# sensor_board2.net
KiCad netlist of a schematic drawn in EAGLE
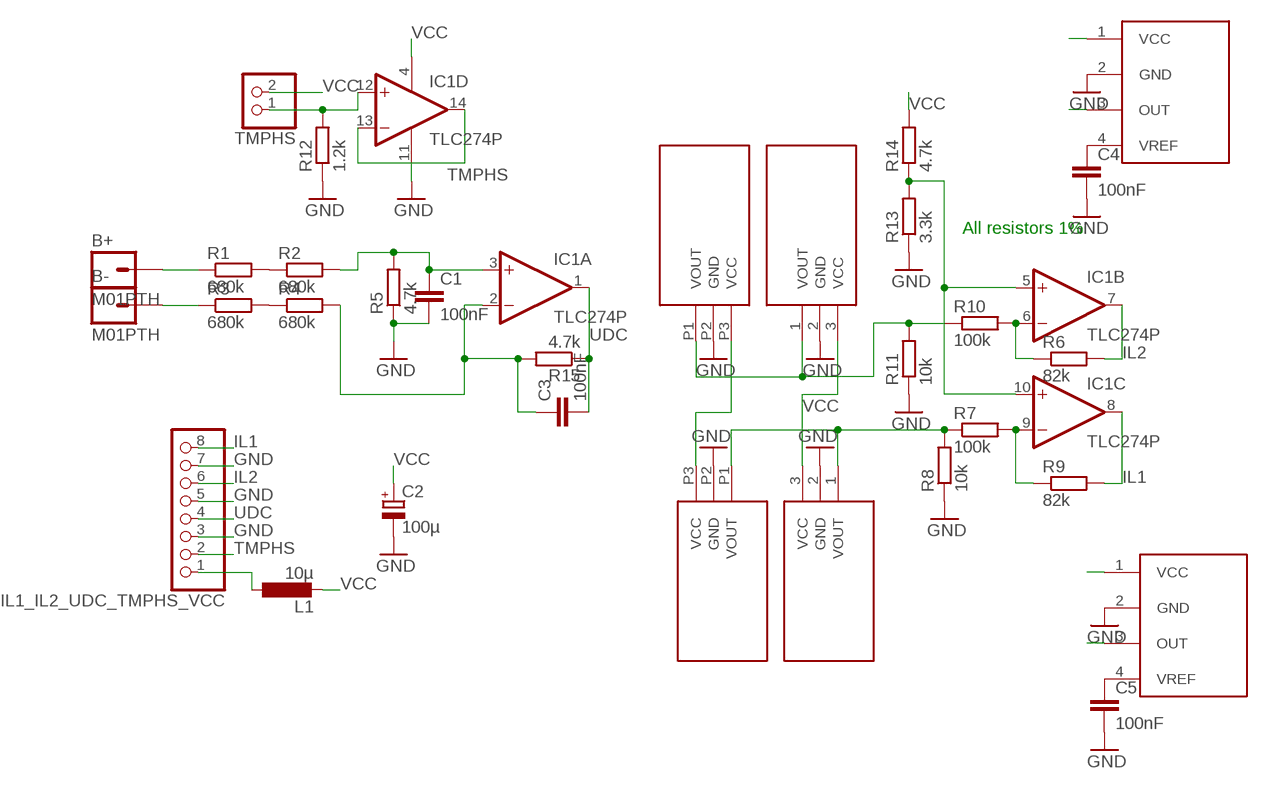
[diagram p0: schematic, sheet 1]

(export (version "E")
  (design (tool "Eeschema 10.0.6"))
  (components
    (comp (ref "B+")
      (value "M01PTH")
      (footprint "eagle-import:1X01")
      (libsource (lib "eagle-import") (part "M01PTH"))
    )
    (comp (ref "B-")
      (value "M01PTH")
      (footprint "eagle-import:1X01")
      (libsource (lib "eagle-import") (part "M01PTH"))
    )
    (comp (ref "C1")
      (value "100nF")
      (footprint "eagle-import:C025-024X044")
      (libsource (lib "eagle-import") (part "C-EU025-024X044"))
    )
    (comp (ref "C2")
      (value "100µ")
      (footprint "eagle-import:E2,5-6E")
      (libsource (lib "eagle-import") (part "CPOL-EUE2,5-6E"))
    )
    (comp (ref "C3")
      (value "100nF")
      (footprint "eagle-import:C025-024X044")
      (libsource (lib "eagle-import") (part "C-EU025-024X044"))
    )
    (comp (ref "C4")
      (value "100nF")
      (footprint "eagle-import:C025-024X044")
      (libsource (lib "eagle-import") (part "C-EU025-024X044"))
    )
    (comp (ref "C5")
      (value "100nF")
      (footprint "eagle-import:C025-024X044")
      (libsource (lib "eagle-import") (part "C-EU025-024X044"))
    )
    (comp (ref "IC1")
      (value "TLC274P")
      (footprint "eagle-import:DIL14")
      (libsource (lib "eagle-import") (part "TLC274P"))
    )
    (comp (ref "IL1_IL2_UDC_TMPHS_VCC")
      (value "PINHD-1X8")
      (footprint "eagle-import:1X08")
      (libsource (lib "eagle-import") (part "PINHD-1X8"))
    )
    (comp (ref "L1")
      (value "10µ")
      (footprint "eagle-import:0207_12")
      (libsource (lib "eagle-import") (part "L-EU0207/12"))
    )
    (comp (ref "R1")
      (value "680k")
      (footprint "eagle-import:0207_10")
      (libsource (lib "eagle-import") (part "R-EU_0207/10"))
    )
    (comp (ref "R2")
      (value "680k")
      (footprint "eagle-import:0207_10")
      (libsource (lib "eagle-import") (part "R-EU_0207/10"))
    )
    (comp (ref "R3")
      (value "680k")
      (footprint "eagle-import:0207_10")
      (libsource (lib "eagle-import") (part "R-EU_0207/10"))
    )
    (comp (ref "R4")
      (value "680k")
      (footprint "eagle-import:0207_10")
      (libsource (lib "eagle-import") (part "R-EU_0207/10"))
    )
    (comp (ref "R5")
      (value "4.7k")
      (footprint "eagle-import:0207_10")
      (libsource (lib "eagle-import") (part "R-EU_0207/10"))
    )
    (comp (ref "R6")
      (value "82k")
      (footprint "eagle-import:0207_10")
      (libsource (lib "eagle-import") (part "R-EU_0207/10"))
    )
    (comp (ref "R7")
      (value "100k")
      (footprint "eagle-import:0207_10")
      (libsource (lib "eagle-import") (part "R-EU_0207/10"))
    )
    (comp (ref "R8")
      (value "10k")
      (footprint "eagle-import:0207_10")
      (libsource (lib "eagle-import") (part "R-EU_0207/10"))
    )
    (comp (ref "R9")
      (value "82k")
      (footprint "eagle-import:0207_10")
      (libsource (lib "eagle-import") (part "R-EU_0207/10"))
    )
    (comp (ref "R10")
      (value "100k")
      (footprint "eagle-import:0207_10")
      (libsource (lib "eagle-import") (part "R-EU_0207/10"))
    )
    (comp (ref "R11")
      (value "10k")
      (footprint "eagle-import:0207_10")
      (libsource (lib "eagle-import") (part "R-EU_0207/10"))
    )
    (comp (ref "R12")
      (value "1.2k")
      (footprint "eagle-import:0207_10")
      (libsource (lib "eagle-import") (part "R-EU_0207/10"))
    )
    (comp (ref "R13")
      (value "3.3k")
      (footprint "eagle-import:0207_10")
      (libsource (lib "eagle-import") (part "R-EU_0207/10"))
    )
    (comp (ref "R14")
      (value "4.7k")
      (footprint "eagle-import:0207_10")
      (libsource (lib "eagle-import") (part "R-EU_0207/10"))
    )
    (comp (ref "R15")
      (value "4.7k")
      (footprint "eagle-import:0207_10")
      (libsource (lib "eagle-import") (part "R-EU_0207/10"))
    )
    (comp (ref "TMPHS")
      (value "PINHD-1X2")
      (footprint "eagle-import:1X02")
      (libsource (lib "eagle-import") (part "PINHD-1X2"))
    )
    (comp (ref "U$1")
      (value "TAMURA_L01Z_S05")
      (footprint "eagle-import:TAMURA_L01Z_S05")
      (libsource (lib "eagle-import") (part "TAMURA_L01Z_S05"))
    )
    (comp (ref "U$2")
      (value "TAMURA_L01Z_S05")
      (footprint "eagle-import:TAMURA_L01Z_S05")
      (libsource (lib "eagle-import") (part "TAMURA_L01Z_S05"))
    )
    (comp (ref "U$3")
      (value "HTFS")
      (footprint "eagle-import:HTFS")
      (libsource (lib "eagle-import") (part "HTFS"))
    )
    (comp (ref "U$4")
      (value "HTFS")
      (footprint "eagle-import:HTFS")
      (libsource (lib "eagle-import") (part "HTFS"))
    )
    (comp (ref "U$5")
      (value "TAMURA_L06P_S05L06P")
      (footprint "eagle-import:TAMURA_L06P_S05")
      (libsource (lib "eagle-import") (part "TAMURA_L06P_S05L06P"))
    )
    (comp (ref "U$6")
      (value "TAMURA_L06P_S05L06P")
      (footprint "eagle-import:TAMURA_L06P_S05")
      (libsource (lib "eagle-import") (part "TAMURA_L06P_S05L06P"))
    )
  )
  (nets
    (net (code "1") (name "/IL1") (class "Default")
      (node (ref "IC1") (pin "8") (pinfunction "OUT_8") (pintype "output"))
      (node (ref "IL1_IL2_UDC_TMPHS_VCC") (pin "8") (pinfunction "8_8") (pintype "passive"))
      (node (ref "R9") (pin "2") (pinfunction "2_2") (pintype "passive"))
    )
    (net (code "2") (name "/IL2") (class "Default")
      (node (ref "IC1") (pin "7") (pinfunction "OUT_7") (pintype "output"))
      (node (ref "IL1_IL2_UDC_TMPHS_VCC") (pin "6") (pinfunction "6_6") (pintype "passive"))
      (node (ref "R6") (pin "2") (pinfunction "2_2") (pintype "passive"))
    )
    (net (code "3") (name "/TMPHS") (class "Default")
      (node (ref "IC1") (pin "13") (pinfunction "-IN_13") (pintype "input"))
      (node (ref "IC1") (pin "14") (pinfunction "OUT_14") (pintype "output"))
      (node (ref "IL1_IL2_UDC_TMPHS_VCC") (pin "2") (pinfunction "2_2") (pintype "passive"))
    )
    (net (code "4") (name "/UDC") (class "Default")
      (node (ref "C3") (pin "2") (pinfunction "2_2") (pintype "passive"))
      (node (ref "IC1") (pin "1") (pinfunction "OUT_1") (pintype "output"))
      (node (ref "IL1_IL2_UDC_TMPHS_VCC") (pin "4") (pinfunction "4_4") (pintype "passive"))
      (node (ref "R15") (pin "1") (pinfunction "1_1") (pintype "passive"))
    )
    (net (code "5") (name "/VCC") (class "Default")
      (node (ref "C2") (pin "+") (pinfunction "+_+") (pintype "passive"))
      (node (ref "IC1") (pin "4") (pinfunction "V+_4") (pintype "power_in"))
      (node (ref "L1") (pin "2") (pinfunction "2_2") (pintype "passive"))
      (node (ref "R14") (pin "2") (pinfunction "2_2") (pintype "passive"))
      (node (ref "TMPHS") (pin "2") (pinfunction "2_2") (pintype "passive"))
      (node (ref "U$1") (pin "3") (pinfunction "VCC_3") (pintype "bidirectional"))
      (node (ref "U$2") (pin "3") (pinfunction "VCC_3") (pintype "bidirectional"))
      (node (ref "U$3") (pin "1") (pinfunction "VCC_1") (pintype "bidirectional"))
      (node (ref "U$4") (pin "1") (pinfunction "VCC_1") (pintype "bidirectional"))
      (node (ref "U$5") (pin "P3") (pinfunction "VCC_P3") (pintype "bidirectional"))
      (node (ref "U$6") (pin "P3") (pinfunction "VCC_P3") (pintype "bidirectional"))
    )
    (net (code "6") (name "/VOUT1") (class "Default")
      (node (ref "R7") (pin "1") (pinfunction "1_1") (pintype "passive"))
      (node (ref "R8") (pin "2") (pinfunction "2_2") (pintype "passive"))
      (node (ref "U$2") (pin "1") (pinfunction "VOUT_1") (pintype "bidirectional"))
      (node (ref "U$4") (pin "3") (pinfunction "OUT_3") (pintype "bidirectional"))
      (node (ref "U$6") (pin "P1") (pinfunction "VOUT_P1") (pintype "bidirectional"))
    )
    (net (code "7") (name "/VOUT2") (class "Default")
      (node (ref "R10") (pin "1") (pinfunction "1_1") (pintype "passive"))
      (node (ref "R11") (pin "2") (pinfunction "2_2") (pintype "passive"))
      (node (ref "U$1") (pin "1") (pinfunction "VOUT_1") (pintype "bidirectional"))
      (node (ref "U$3") (pin "3") (pinfunction "OUT_3") (pintype "bidirectional"))
      (node (ref "U$5") (pin "P1") (pinfunction "VOUT_P1") (pintype "bidirectional"))
    )
    (net (code "8") (name "GND") (class "Default")
      (node (ref "C1") (pin "2") (pinfunction "2_2") (pintype "passive"))
      (node (ref "C2") (pin "-") (pinfunction "-_-") (pintype "passive"))
      (node (ref "C4") (pin "2") (pinfunction "2_2") (pintype "passive"))
      (node (ref "C5") (pin "2") (pinfunction "2_2") (pintype "passive"))
      (node (ref "IC1") (pin "11") (pinfunction "V-_11") (pintype "power_in"))
      (node (ref "IL1_IL2_UDC_TMPHS_VCC") (pin "3") (pinfunction "3_3") (pintype "passive"))
      (node (ref "IL1_IL2_UDC_TMPHS_VCC") (pin "5") (pinfunction "5_5") (pintype "passive"))
      (node (ref "IL1_IL2_UDC_TMPHS_VCC") (pin "7") (pinfunction "7_7") (pintype "passive"))
      (node (ref "R11") (pin "1") (pinfunction "1_1") (pintype "passive"))
      (node (ref "R12") (pin "1") (pinfunction "1_1") (pintype "passive"))
      (node (ref "R13") (pin "1") (pinfunction "1_1") (pintype "passive"))
      (node (ref "R5") (pin "1") (pinfunction "1_1") (pintype "passive"))
      (node (ref "R8") (pin "1") (pinfunction "1_1") (pintype "passive"))
      (node (ref "U$1") (pin "2") (pinfunction "GND_2") (pintype "bidirectional"))
      (node (ref "U$2") (pin "2") (pinfunction "GND_2") (pintype "bidirectional"))
      (node (ref "U$3") (pin "2") (pinfunction "GND_2") (pintype "bidirectional"))
      (node (ref "U$4") (pin "2") (pinfunction "GND_2") (pintype "bidirectional"))
      (node (ref "U$5") (pin "P2") (pinfunction "GND_P2") (pintype "bidirectional"))
      (node (ref "U$6") (pin "P2") (pinfunction "GND_P2") (pintype "bidirectional"))
    )
    (net (code "9") (name "Net-(B+-Pad1)") (class "Default")
      (node (ref "B+") (pin "1") (pinfunction "1_1") (pintype "passive"))
      (node (ref "R1") (pin "1") (pinfunction "1_1") (pintype "passive"))
    )
    (net (code "10") (name "Net-(B--Pad1)") (class "Default")
      (node (ref "B-") (pin "1") (pinfunction "1_1") (pintype "passive"))
      (node (ref "R3") (pin "1") (pinfunction "1_1") (pintype "passive"))
    )
    (net (code "11") (name "Net-(IC1A-+IN)") (class "Default")
      (node (ref "C1") (pin "1") (pinfunction "1_1") (pintype "passive"))
      (node (ref "IC1") (pin "3") (pinfunction "+IN_3") (pintype "input"))
      (node (ref "R2") (pin "2") (pinfunction "2_2") (pintype "passive"))
      (node (ref "R5") (pin "2") (pinfunction "2_2") (pintype "passive"))
    )
    (net (code "12") (name "Net-(IC1A--IN)") (class "Default")
      (node (ref "C3") (pin "1") (pinfunction "1_1") (pintype "passive"))
      (node (ref "IC1") (pin "2") (pinfunction "-IN_2") (pintype "input"))
      (node (ref "R15") (pin "2") (pinfunction "2_2") (pintype "passive"))
      (node (ref "R4") (pin "2") (pinfunction "2_2") (pintype "passive"))
    )
    (net (code "13") (name "Net-(IC1B-+IN)") (class "Default")
      (node (ref "IC1") (pin "10") (pinfunction "+IN_10") (pintype "input"))
      (node (ref "IC1") (pin "5") (pinfunction "+IN_5") (pintype "input"))
      (node (ref "R13") (pin "2") (pinfunction "2_2") (pintype "passive"))
      (node (ref "R14") (pin "1") (pinfunction "1_1") (pintype "passive"))
    )
    (net (code "14") (name "Net-(IC1B--IN)") (class "Default")
      (node (ref "IC1") (pin "6") (pinfunction "-IN_6") (pintype "input"))
      (node (ref "R10") (pin "2") (pinfunction "2_2") (pintype "passive"))
      (node (ref "R6") (pin "1") (pinfunction "1_1") (pintype "passive"))
    )
    (net (code "15") (name "Net-(IC1C--IN)") (class "Default")
      (node (ref "IC1") (pin "9") (pinfunction "-IN_9") (pintype "input"))
      (node (ref "R7") (pin "2") (pinfunction "2_2") (pintype "passive"))
      (node (ref "R9") (pin "1") (pinfunction "1_1") (pintype "passive"))
    )
    (net (code "16") (name "Net-(IC1D-+IN)") (class "Default")
      (node (ref "IC1") (pin "12") (pinfunction "+IN_12") (pintype "input"))
      (node (ref "R12") (pin "2") (pinfunction "2_2") (pintype "passive"))
      (node (ref "TMPHS") (pin "1") (pinfunction "1_1") (pintype "passive"))
    )
    (net (code "17") (name "Net-(IL1_IL2_UDC_TMPHS_VCC-Pad1)") (class "Default")
      (node (ref "IL1_IL2_UDC_TMPHS_VCC") (pin "1") (pinfunction "1_1") (pintype "passive"))
      (node (ref "L1") (pin "1") (pinfunction "1_1") (pintype "passive"))
    )
    (net (code "18") (name "Net-(R1-Pad2)") (class "Default")
      (node (ref "R1") (pin "2") (pinfunction "2_2") (pintype "passive"))
      (node (ref "R2") (pin "1") (pinfunction "1_1") (pintype "passive"))
    )
    (net (code "19") (name "Net-(R3-Pad2)") (class "Default")
      (node (ref "R3") (pin "2") (pinfunction "2_2") (pintype "passive"))
      (node (ref "R4") (pin "1") (pinfunction "1_1") (pintype "passive"))
    )
    (net (code "20") (name "Net-(U$3-VREF)") (class "Default")
      (node (ref "C4") (pin "1") (pinfunction "1_1") (pintype "passive"))
      (node (ref "U$3") (pin "4") (pinfunction "VREF_4") (pintype "bidirectional"))
    )
    (net (code "21") (name "Net-(U$4-VREF)") (class "Default")
      (node (ref "C5") (pin "1") (pinfunction "1_1") (pintype "passive"))
      (node (ref "U$4") (pin "4") (pinfunction "VREF_4") (pintype "bidirectional"))
    )
  )
)
